# Sheet2.net
KiCad netlist of a schematic drawn in Altium Designer
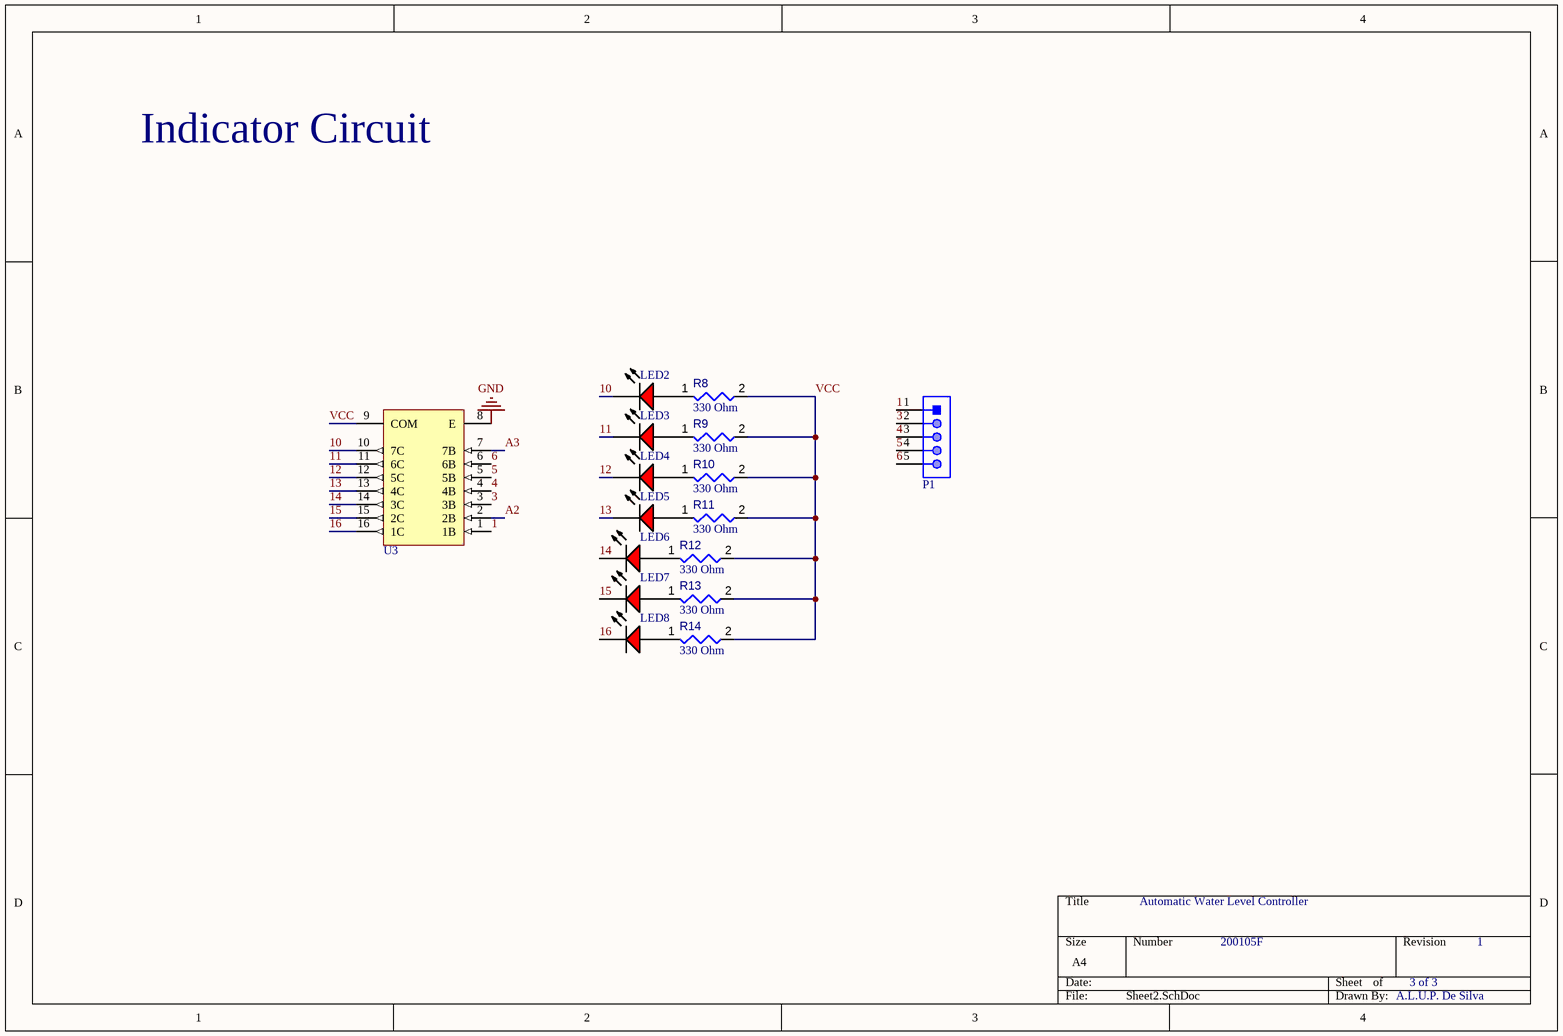
[diagram p0: Sheet2.SchDoc]

(export (version "E")
  (design (tool "Eeschema 10.0.6"))
  (components
    (comp (ref "LED2")
      (value "HLMP-3301")
      (footprint "AVAG-HLMP-3301-2")
      (description "T-1 3/4 (5 mm) Diffused LED Lamp, 1.9 V, -40 to 100 degC, 2-Pin THD, RoHS, Bulk")
      (fields (field (name "MANUFACTURER") "Avago"))
      (libsource (lib "Altium Content Vault") (part "LED-RED-K1A2-2"))
    )
    (comp (ref "LED3")
      (value "HLMP-3301")
      (footprint "AVAG-HLMP-3301-2")
      (description "T-1 3/4 (5 mm) Diffused LED Lamp, 1.9 V, -40 to 100 degC, 2-Pin THD, RoHS, Bulk")
      (fields (field (name "MANUFACTURER") "Avago"))
      (libsource (lib "Altium Content Vault") (part "LED-RED-K1A2-2"))
    )
    (comp (ref "LED4")
      (value "HLMP-3301")
      (footprint "AVAG-HLMP-3301-2")
      (description "T-1 3/4 (5 mm) Diffused LED Lamp, 1.9 V, -40 to 100 degC, 2-Pin THD, RoHS, Bulk")
      (fields (field (name "MANUFACTURER") "Avago"))
      (libsource (lib "Altium Content Vault") (part "LED-RED-K1A2-2"))
    )
    (comp (ref "LED5")
      (value "HLMP-3301")
      (footprint "AVAG-HLMP-3301-2")
      (description "T-1 3/4 (5 mm) Diffused LED Lamp, 1.9 V, -40 to 100 degC, 2-Pin THD, RoHS, Bulk")
      (fields (field (name "MANUFACTURER") "Avago"))
      (libsource (lib "Altium Content Vault") (part "LED-RED-K1A2-2"))
    )
    (comp (ref "LED6")
      (value "HLMP-3301")
      (footprint "AVAG-HLMP-3301-2")
      (description "T-1 3/4 (5 mm) Diffused LED Lamp, 1.9 V, -40 to 100 degC, 2-Pin THD, RoHS, Bulk")
      (fields (field (name "MANUFACTURER") "Avago"))
      (libsource (lib "Altium Content Vault") (part "LED-RED-K1A2-2"))
    )
    (comp (ref "LED7")
      (value "HLMP-3301")
      (footprint "AVAG-HLMP-3301-2")
      (description "T-1 3/4 (5 mm) Diffused LED Lamp, 1.9 V, -40 to 100 degC, 2-Pin THD, RoHS, Bulk")
      (fields (field (name "MANUFACTURER") "Avago"))
      (libsource (lib "Altium Content Vault") (part "LED-RED-K1A2-2"))
    )
    (comp (ref "LED8")
      (value "HLMP-3301")
      (footprint "AVAG-HLMP-3301-2")
      (description "T-1 3/4 (5 mm) Diffused LED Lamp, 1.9 V, -40 to 100 degC, 2-Pin THD, RoHS, Bulk")
      (fields (field (name "MANUFACTURER") "Avago"))
      (libsource (lib "Altium Content Vault") (part "LED-RED-K1A2-2"))
    )
    (comp (ref "P1")
      (value "691311700105")
      (footprint "691311700105")
      (description "Serie 3117 - 5.00mm Close Vertical PCB Header WR-TBL, 5 pin")
      (fields (field (name "MANUFACTURER") "Wurth Elektronik") (field (name "PUBLISHER") "WurthElektronik"))
      (libsource (lib "Altium Content Vault") (part "WE-CN-1P-M-R5"))
    )
    (comp (ref "R8")
      (value "330 Ohm")
      (footprint "RESA60-630X240")
      (description "Axial Resistor, 475 KOhm, +/- 1%, 0.25 W, -55 to 155 degC, 2-Pin THD, RoHS, Bulk")
      (fields (field (name "POWER") "250mW") (field (name "TOLERANCE") "1%"))
      (libsource (lib "Ulindu's Workspace") (part "RES-2"))
    )
    (comp (ref "R9")
      (value "330 Ohm")
      (footprint "RESA60-630X240")
      (description "Axial Resistor, 475 KOhm, +/- 1%, 0.25 W, -55 to 155 degC, 2-Pin THD, RoHS, Bulk")
      (fields (field (name "POWER") "250mW") (field (name "TOLERANCE") "1%"))
      (libsource (lib "Ulindu's Workspace") (part "RES-2"))
    )
    (comp (ref "R10")
      (value "330 Ohm")
      (footprint "RESA60-630X240")
      (description "Axial Resistor, 475 KOhm, +/- 1%, 0.25 W, -55 to 155 degC, 2-Pin THD, RoHS, Bulk")
      (fields (field (name "POWER") "250mW") (field (name "TOLERANCE") "1%"))
      (libsource (lib "Ulindu's Workspace") (part "RES-2"))
    )
    (comp (ref "R11")
      (value "330 Ohm")
      (footprint "RESA60-630X240")
      (description "Axial Resistor, 475 KOhm, +/- 1%, 0.25 W, -55 to 155 degC, 2-Pin THD, RoHS, Bulk")
      (fields (field (name "POWER") "250mW") (field (name "TOLERANCE") "1%"))
      (libsource (lib "Ulindu's Workspace") (part "RES-2"))
    )
    (comp (ref "R12")
      (value "330 Ohm")
      (footprint "RESA60-630X240")
      (description "Axial Resistor, 475 KOhm, +/- 1%, 0.25 W, -55 to 155 degC, 2-Pin THD, RoHS, Bulk")
      (fields (field (name "POWER") "250mW") (field (name "TOLERANCE") "1%"))
      (libsource (lib "Ulindu's Workspace") (part "RES-2"))
    )
    (comp (ref "R13")
      (value "330 Ohm")
      (footprint "RESA60-630X240")
      (description "Axial Resistor, 475 KOhm, +/- 1%, 0.25 W, -55 to 155 degC, 2-Pin THD, RoHS, Bulk")
      (fields (field (name "POWER") "250mW") (field (name "TOLERANCE") "1%"))
      (libsource (lib "Ulindu's Workspace") (part "RES-2"))
    )
    (comp (ref "R14")
      (value "330 Ohm")
      (footprint "RESA60-630X240")
      (description "Axial Resistor, 475 KOhm, +/- 1%, 0.25 W, -55 to 155 degC, 2-Pin THD, RoHS, Bulk")
      (fields (field (name "POWER") "250mW") (field (name "TOLERANCE") "1%"))
      (libsource (lib "Ulindu's Workspace") (part "RES-2"))
    )
    (comp (ref "U3")
      (value "ULN2003AN")
      (footprint "N0016A")
      (fields (field (name "MANUFACTURER") "TexasInstruments"))
      (libsource (lib "Altium Content Vault") (part "TI-ULN2003A-PDIP_N-16"))
    )
  )
  (nets
    (net (code "1") (name "/1") (class "Default")
      (node (ref "P1") (pin "1") (pinfunction "1_1") (pintype "passive"))
      (node (ref "U3") (pin "1") (pinfunction "1B_1") (pintype "input"))
    )
    (net (code "2") (name "/3") (class "Default")
      (node (ref "P1") (pin "2") (pinfunction "2_2") (pintype "passive"))
      (node (ref "U3") (pin "3") (pinfunction "3B_3") (pintype "input"))
    )
    (net (code "3") (name "/4") (class "Default")
      (node (ref "P1") (pin "3") (pinfunction "3_3") (pintype "passive"))
      (node (ref "U3") (pin "4") (pinfunction "4B_4") (pintype "input"))
    )
    (net (code "4") (name "/5") (class "Default")
      (node (ref "P1") (pin "4") (pinfunction "4_4") (pintype "passive"))
      (node (ref "U3") (pin "5") (pinfunction "5B_5") (pintype "input"))
    )
    (net (code "5") (name "/6") (class "Default")
      (node (ref "P1") (pin "5") (pinfunction "5_5") (pintype "passive"))
      (node (ref "U3") (pin "6") (pinfunction "6B_6") (pintype "input"))
    )
    (net (code "6") (name "/10") (class "Default")
      (node (ref "LED2") (pin "1") (pinfunction "K_1") (pintype "passive"))
      (node (ref "U3") (pin "10") (pinfunction "7C_10") (pintype "output"))
    )
    (net (code "7") (name "/11") (class "Default")
      (node (ref "LED3") (pin "1") (pinfunction "K_1") (pintype "passive"))
      (node (ref "U3") (pin "11") (pinfunction "6C_11") (pintype "output"))
    )
    (net (code "8") (name "/12") (class "Default")
      (node (ref "LED4") (pin "1") (pinfunction "K_1") (pintype "passive"))
      (node (ref "U3") (pin "12") (pinfunction "5C_12") (pintype "output"))
    )
    (net (code "9") (name "/13") (class "Default")
      (node (ref "LED5") (pin "1") (pinfunction "K_1") (pintype "passive"))
      (node (ref "U3") (pin "13") (pinfunction "4C_13") (pintype "output"))
    )
    (net (code "10") (name "/14") (class "Default")
      (node (ref "LED6") (pin "1") (pinfunction "K_1") (pintype "passive"))
      (node (ref "U3") (pin "14") (pinfunction "3C_14") (pintype "output"))
    )
    (net (code "11") (name "/15") (class "Default")
      (node (ref "LED7") (pin "1") (pinfunction "K_1") (pintype "passive"))
      (node (ref "U3") (pin "15") (pinfunction "2C_15") (pintype "output"))
    )
    (net (code "12") (name "/16") (class "Default")
      (node (ref "LED8") (pin "1") (pinfunction "K_1") (pintype "passive"))
      (node (ref "U3") (pin "16") (pinfunction "1C_16") (pintype "output"))
    )
    (net (code "13") (name "/A2") (class "Default")
      (node (ref "U3") (pin "2") (pinfunction "2B_2") (pintype "input"))
    )
    (net (code "14") (name "/A3") (class "Default")
      (node (ref "U3") (pin "7") (pinfunction "7B_7") (pintype "input"))
    )
    (net (code "15") (name "/VCC") (class "Default")
      (node (ref "R10") (pin "2") (pinfunction "2_2") (pintype "passive"))
      (node (ref "R11") (pin "2") (pinfunction "2_2") (pintype "passive"))
      (node (ref "R12") (pin "2") (pinfunction "2_2") (pintype "passive"))
      (node (ref "R13") (pin "2") (pinfunction "2_2") (pintype "passive"))
      (node (ref "R14") (pin "2") (pinfunction "2_2") (pintype "passive"))
      (node (ref "R8") (pin "2") (pinfunction "2_2") (pintype "passive"))
      (node (ref "R9") (pin "2") (pinfunction "2_2") (pintype "passive"))
      (node (ref "U3") (pin "9") (pinfunction "COM_9") (pintype "passive"))
    )
    (net (code "16") (name "GND") (class "Default")
      (node (ref "U3") (pin "8") (pinfunction "E_8") (pintype "passive"))
    )
    (net (code "17") (name "Net-(LED2-A)") (class "Default")
      (node (ref "LED2") (pin "2") (pinfunction "A_2") (pintype "passive"))
      (node (ref "R8") (pin "1") (pinfunction "1_1") (pintype "passive"))
    )
    (net (code "18") (name "Net-(LED3-A)") (class "Default")
      (node (ref "LED3") (pin "2") (pinfunction "A_2") (pintype "passive"))
      (node (ref "R9") (pin "1") (pinfunction "1_1") (pintype "passive"))
    )
    (net (code "19") (name "Net-(LED4-A)") (class "Default")
      (node (ref "LED4") (pin "2") (pinfunction "A_2") (pintype "passive"))
      (node (ref "R10") (pin "1") (pinfunction "1_1") (pintype "passive"))
    )
    (net (code "20") (name "Net-(LED5-A)") (class "Default")
      (node (ref "LED5") (pin "2") (pinfunction "A_2") (pintype "passive"))
      (node (ref "R11") (pin "1") (pinfunction "1_1") (pintype "passive"))
    )
    (net (code "21") (name "Net-(LED6-A)") (class "Default")
      (node (ref "LED6") (pin "2") (pinfunction "A_2") (pintype "passive"))
      (node (ref "R12") (pin "1") (pinfunction "1_1") (pintype "passive"))
    )
    (net (code "22") (name "Net-(LED7-A)") (class "Default")
      (node (ref "LED7") (pin "2") (pinfunction "A_2") (pintype "passive"))
      (node (ref "R13") (pin "1") (pinfunction "1_1") (pintype "passive"))
    )
    (net (code "23") (name "Net-(LED8-A)") (class "Default")
      (node (ref "LED8") (pin "2") (pinfunction "A_2") (pintype "passive"))
      (node (ref "R14") (pin "1") (pinfunction "1_1") (pintype "passive"))
    )
  )
)
